# AS504D_Sch.net
KiCad netlist of a schematic drawn in Altium Designer
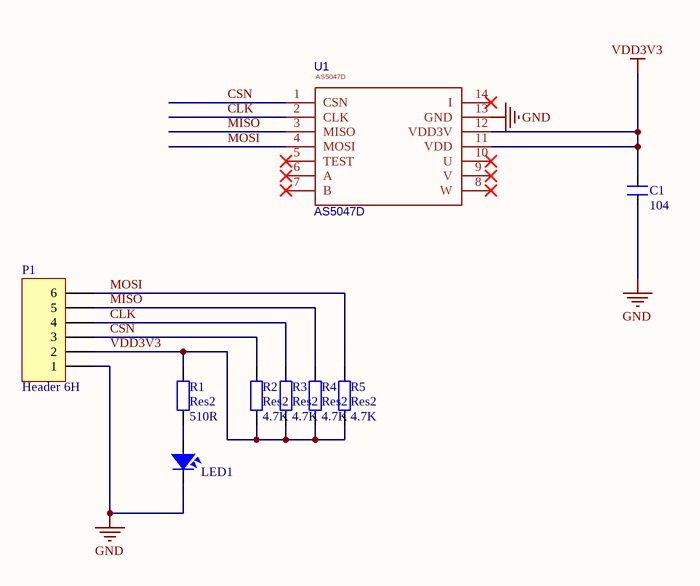
[diagram p0: AS504D_Sch.SchDoc]

(export (version "E")
  (design (tool "Eeschema 10.0.6"))
  (components
    (comp (ref "C1")
      (value "104")
      (footprint "CN2")
      (description "Cap np 104 => 105pF")
      (libsource (lib "syhaunguyen") (part "CN2"))
    )
    (comp (ref "LED1")
      (value "LED")
      (footprint "LED-3")
      (description "LED Single colour Green and Red")
      (libsource (lib "syhaunguyen") (part "LED"))
    )
    (comp (ref "P1")
      (value "Header 6H")
      (footprint "HDR1X6H")
      (description "Header, 6-Pin, Right Angle")
      (fields (field (name "PUBLISHER") "Altium Limited"))
      (libsource (lib "Miscellaneous Connectors") (part "Header 6H"))
    )
    (comp (ref "R1")
      (value "Res2")
      (footprint "AXIAL-0.4")
      (description "Resistor")
      (fields (field (name "ALTIUM_VALUE") "510R") (field (name "PUBLISHER") "Altium Limited"))
      (libsource (lib "") (part "Res2_1"))
    )
    (comp (ref "R2")
      (value "Res2")
      (footprint "AXIAL-0.4")
      (description "Resistor")
      (fields (field (name "ALTIUM_VALUE") "4.7K") (field (name "PUBLISHER") "Altium Limited"))
      (libsource (lib "Miscellaneous Devices") (part "Res2"))
    )
    (comp (ref "R3")
      (value "Res2")
      (footprint "AXIAL-0.4")
      (description "Resistor")
      (fields (field (name "ALTIUM_VALUE") "4.7K") (field (name "PUBLISHER") "Altium Limited"))
      (libsource (lib "Miscellaneous Devices") (part "Res2"))
    )
    (comp (ref "R4")
      (value "Res2")
      (footprint "AXIAL-0.4")
      (description "Resistor")
      (fields (field (name "ALTIUM_VALUE") "4.7K") (field (name "PUBLISHER") "Altium Limited"))
      (libsource (lib "Miscellaneous Devices") (part "Res2"))
    )
    (comp (ref "R5")
      (value "Res2")
      (footprint "AXIAL-0.4")
      (description "Resistor")
      (fields (field (name "ALTIUM_VALUE") "4.7K") (field (name "PUBLISHER") "Altium Limited"))
      (libsource (lib "Miscellaneous Devices") (part "Res2"))
    )
    (comp (ref "U1")
      (value "AS5047D")
      (footprint "TSSOP14")
      (fields (field (name "BOM_MANUFACTURER PART") "?"))
      (libsource (lib "mySch") (part "AS5047D"))
    )
  )
  (nets
    (net (code "1") (name "/CLK") (class "Default")
      (node (ref "P1") (pin "4") (pinfunction "4_4") (pintype "passive"))
      (node (ref "R3") (pin "1") (pinfunction "1_1") (pintype "passive"))
      (node (ref "U1") (pin "2") (pinfunction "CLK_2") (pintype "passive"))
    )
    (net (code "2") (name "/CSN") (class "Default")
      (node (ref "P1") (pin "3") (pinfunction "3_3") (pintype "passive"))
      (node (ref "R2") (pin "1") (pinfunction "1_1") (pintype "passive"))
      (node (ref "U1") (pin "1") (pinfunction "CSN_1") (pintype "passive"))
    )
    (net (code "3") (name "/MISO") (class "Default")
      (node (ref "P1") (pin "5") (pinfunction "5_5") (pintype "passive"))
      (node (ref "R4") (pin "1") (pinfunction "1_1") (pintype "passive"))
      (node (ref "U1") (pin "3") (pinfunction "MISO_3") (pintype "passive"))
    )
    (net (code "4") (name "/MOSI") (class "Default")
      (node (ref "P1") (pin "6") (pinfunction "6_6") (pintype "passive"))
      (node (ref "R5") (pin "1") (pinfunction "1_1") (pintype "passive"))
      (node (ref "U1") (pin "4") (pinfunction "MOSI_4") (pintype "passive"))
    )
    (net (code "5") (name "GND") (class "Default")
      (node (ref "C1") (pin "1") (pinfunction "1_1") (pintype "passive"))
      (node (ref "LED1") (pin "2") (pinfunction "2_2") (pintype "passive"))
      (node (ref "P1") (pin "1") (pinfunction "1_1") (pintype "passive"))
      (node (ref "U1") (pin "13") (pinfunction "GND_13") (pintype "passive"))
    )
    (net (code "6") (name "Net-(LED1-Pad1)") (class "Default")
      (node (ref "LED1") (pin "1") (pinfunction "1_1") (pintype "passive"))
      (node (ref "R1") (pin "1") (pinfunction "1_1") (pintype "passive"))
    )
    (net (code "7") (name "VDD3V3") (class "Default")
      (node (ref "C1") (pin "2") (pinfunction "2_2") (pintype "passive"))
      (node (ref "P1") (pin "2") (pinfunction "2_2") (pintype "passive"))
      (node (ref "R1") (pin "2") (pinfunction "2_2") (pintype "passive"))
      (node (ref "R2") (pin "2") (pinfunction "2_2") (pintype "passive"))
      (node (ref "R3") (pin "2") (pinfunction "2_2") (pintype "passive"))
      (node (ref "R4") (pin "2") (pinfunction "2_2") (pintype "passive"))
      (node (ref "R5") (pin "2") (pinfunction "2_2") (pintype "passive"))
      (node (ref "U1") (pin "11") (pinfunction "VDD_11") (pintype "passive"))
      (node (ref "U1") (pin "12") (pinfunction "VDD3V_12") (pintype "passive"))
    )
    (net (code "8") (name "unconnected-(U1-A-Pad6)") (class "Default")
      (node (ref "U1") (pin "6") (pinfunction "A_6") (pintype "passive+no_connect"))
    )
    (net (code "9") (name "unconnected-(U1-B-Pad7)") (class "Default")
      (node (ref "U1") (pin "7") (pinfunction "B_7") (pintype "passive+no_connect"))
    )
    (net (code "10") (name "unconnected-(U1-I-Pad14)") (class "Default")
      (node (ref "U1") (pin "14") (pinfunction "I_14") (pintype "passive+no_connect"))
    )
    (net (code "11") (name "unconnected-(U1-TEST-Pad5)") (class "Default")
      (node (ref "U1") (pin "5") (pinfunction "TEST_5") (pintype "passive+no_connect"))
    )
    (net (code "12") (name "unconnected-(U1-U-Pad10)") (class "Default")
      (node (ref "U1") (pin "10") (pinfunction "U_10") (pintype "passive+no_connect"))
    )
    (net (code "13") (name "unconnected-(U1-V-Pad9)") (class "Default")
      (node (ref "U1") (pin "9") (pinfunction "V_9") (pintype "passive+no_connect"))
    )
    (net (code "14") (name "unconnected-(U1-W-Pad8)") (class "Default")
      (node (ref "U1") (pin "8") (pinfunction "W_8") (pintype "passive+no_connect"))
    )
  )
)
